# Servo_CAN_Node_REV-A.net
KiCad netlist of a schematic drawn in EAGLE
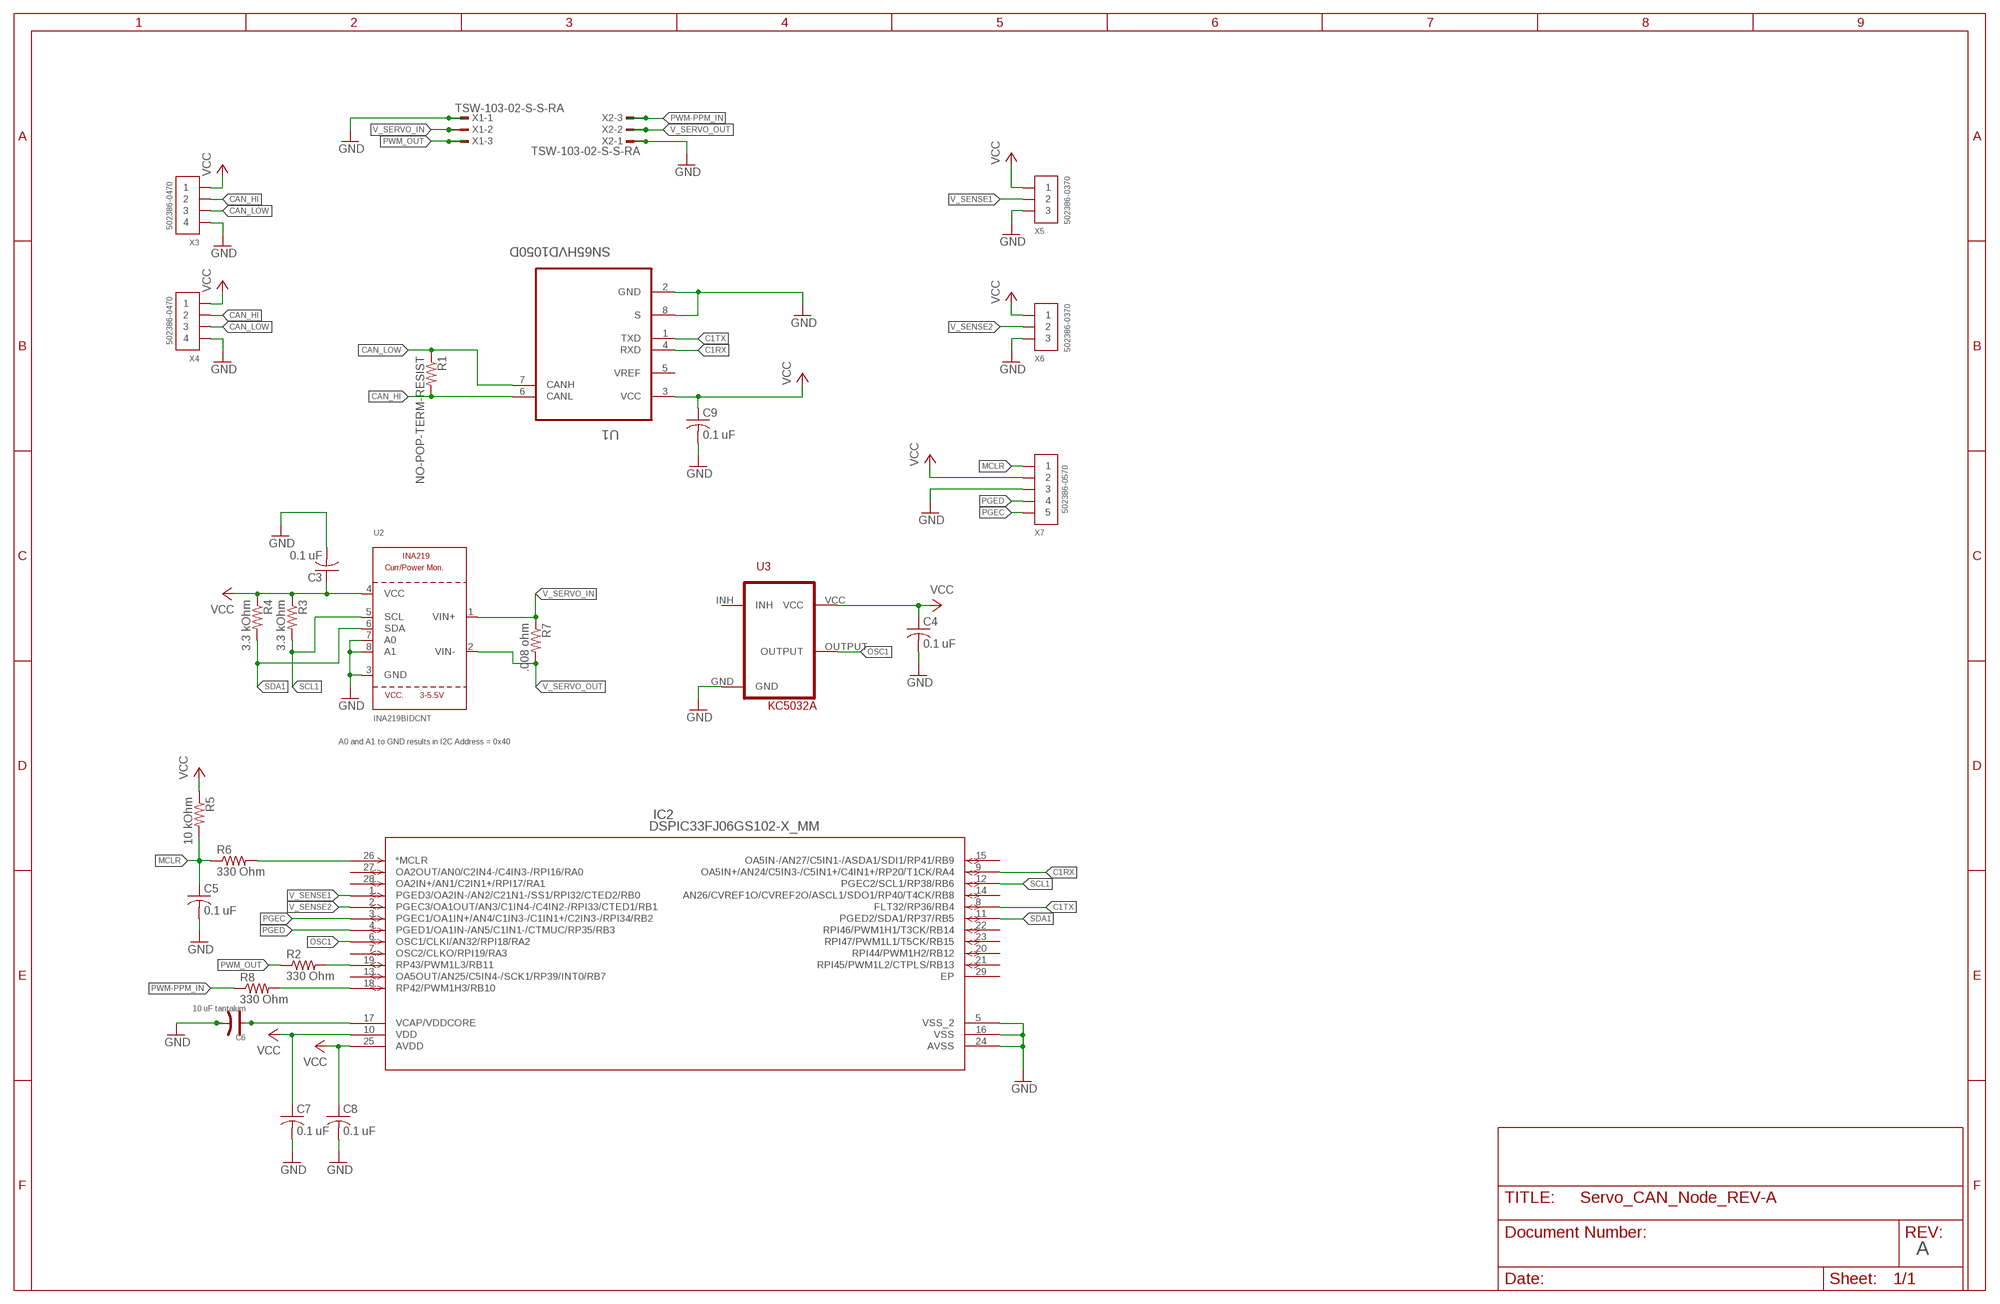
[diagram p0: schematic, sheet 1]

(export (version "E")
  (design (tool "Eeschema 10.0.6"))
  (components
    (comp (ref "C3")
      (value "0.1 uF")
      (footprint "eagle-import:C0402")
      (libsource (lib "eagle-import") (part "C-USC0402"))
    )
    (comp (ref "C4")
      (value "0.1 uF")
      (footprint "eagle-import:C0402")
      (libsource (lib "eagle-import") (part "C-USC0402"))
    )
    (comp (ref "C5")
      (value "0.1 uF")
      (footprint "eagle-import:C0402")
      (libsource (lib "eagle-import") (part "C-USC0402"))
    )
    (comp (ref "C6")
      (value "10 uF tantalum")
      (footprint "eagle-import:AVX-A")
      (libsource (lib "eagle-import") (part "CAP-POLAR-AVX-A"))
    )
    (comp (ref "C7")
      (value "0.1 uF")
      (footprint "eagle-import:C0402")
      (libsource (lib "eagle-import") (part "C-USC0402"))
    )
    (comp (ref "C8")
      (value "0.1 uF")
      (footprint "eagle-import:C0402")
      (libsource (lib "eagle-import") (part "C-USC0402"))
    )
    (comp (ref "C9")
      (value "0.1 uF")
      (footprint "eagle-import:C0402")
      (libsource (lib "eagle-import") (part "C-USC0402"))
    )
    (comp (ref "IC2")
      (value "DSPIC33FJ06GS102-X_MM")
      (footprint "eagle-import:QFN-S28_6X6MC")
      (libsource (lib "eagle-import") (part "DSPIC33FJ06GS102-X_MM"))
    )
    (comp (ref "R1")
      (value "NO-POP-TERM-RESIST")
      (footprint "eagle-import:R0402")
      (libsource (lib "eagle-import") (part "R-US_R0402"))
    )
    (comp (ref "R2")
      (value "330 Ohm")
      (footprint "eagle-import:R0402")
      (libsource (lib "eagle-import") (part "R-US_R0402"))
    )
    (comp (ref "R3")
      (value "3.3 kOhm")
      (footprint "eagle-import:R0402")
      (libsource (lib "eagle-import") (part "R-US_R0402"))
    )
    (comp (ref "R4")
      (value "3.3 kOhm")
      (footprint "eagle-import:R0402")
      (libsource (lib "eagle-import") (part "R-US_R0402"))
    )
    (comp (ref "R5")
      (value "10 kOhm")
      (footprint "eagle-import:R0402")
      (libsource (lib "eagle-import") (part "R-US_R0402"))
    )
    (comp (ref "R6")
      (value "330 Ohm")
      (footprint "eagle-import:R0402")
      (libsource (lib "eagle-import") (part "R-US_R0402"))
    )
    (comp (ref "R7")
      (value ".008 ohm")
      (footprint "eagle-import:R0805")
      (libsource (lib "eagle-import") (part "R-US_R0805"))
    )
    (comp (ref "R8")
      (value "330 Ohm")
      (footprint "eagle-import:R0402")
      (libsource (lib "eagle-import") (part "R-US_R0402"))
    )
    (comp (ref "U1")
      (value "SN65HVD1050D")
      (footprint "eagle-import:SOIC127P600X175-8N")
      (libsource (lib "eagle-import") (part "SN65HVD1050D"))
    )
    (comp (ref "U2")
      (value "INA219BIDCNT")
      (footprint "eagle-import:SOT23-8")
      (libsource (lib "eagle-import") (part "INA219"))
    )
    (comp (ref "U3")
      (value "KC5032A")
      (footprint "eagle-import:KC5032A")
      (libsource (lib "eagle-import") (part "KC5032A"))
    )
    (comp (ref "X1")
      (value "TSW-103-02-S-S-RA")
      (footprint "eagle-import:TSW-103-02-S-S-RA")
      (libsource (lib "eagle-import") (part "TSW-103-02-S-S-RA"))
    )
    (comp (ref "X2")
      (value "TSW-103-02-S-S-RA")
      (footprint "eagle-import:TSW-103-02-S-S-RA")
      (libsource (lib "eagle-import") (part "TSW-103-02-S-S-RA"))
    )
    (comp (ref "X3")
      (value "CONN_4-1-502386")
      (footprint "eagle-import:CM-502386-04")
      (libsource (lib "eagle-import") (part "CONN_4-1-502386"))
    )
    (comp (ref "X4")
      (value "CONN_4-1-502386")
      (footprint "eagle-import:CM-502386-04")
      (libsource (lib "eagle-import") (part "CONN_4-1-502386"))
    )
    (comp (ref "X5")
      (value "CONN_3-1-502386")
      (footprint "eagle-import:CM-502386-03")
      (libsource (lib "eagle-import") (part "CONN_3-1-502386"))
    )
    (comp (ref "X6")
      (value "CONN_3-1-502386")
      (footprint "eagle-import:CM-502386-03")
      (libsource (lib "eagle-import") (part "CONN_3-1-502386"))
    )
    (comp (ref "X7")
      (value "CONN_5-1-502386")
      (footprint "eagle-import:CM-502386-05")
      (libsource (lib "eagle-import") (part "CONN_5-1-502386"))
    )
  )
  (nets
    (net (code "1") (name "C1RX") (class "Default")
      (node (ref "IC2") (pin "9") (pinfunction "OA5IN+/AN24/C5IN3-/C5IN1+/C4IN1+/RP20/T1CK/RA4_9") (pintype "bidirectional"))
      (node (ref "U1") (pin "4") (pinfunction "RXD_4") (pintype "input"))
    )
    (net (code "2") (name "C1TX") (class "Default")
      (node (ref "IC2") (pin "8") (pinfunction "FLT32/RP36/RB4_8") (pintype "bidirectional"))
      (node (ref "U1") (pin "1") (pinfunction "TXD_1") (pintype "input"))
    )
    (net (code "3") (name "CAN_HI") (class "Default")
      (node (ref "R1") (pin "2") (pinfunction "2_2") (pintype "passive"))
      (node (ref "U1") (pin "6") (pinfunction "CANL_6") (pintype "output"))
      (node (ref "X3") (pin "2") (pinfunction "2_2") (pintype "bidirectional"))
      (node (ref "X4") (pin "2") (pinfunction "2_2") (pintype "bidirectional"))
    )
    (net (code "4") (name "CAN_LOW") (class "Default")
      (node (ref "R1") (pin "1") (pinfunction "1_1") (pintype "passive"))
      (node (ref "U1") (pin "7") (pinfunction "CANH_7") (pintype "output"))
      (node (ref "X3") (pin "3") (pinfunction "3_3") (pintype "bidirectional"))
      (node (ref "X4") (pin "3") (pinfunction "3_3") (pintype "bidirectional"))
    )
    (net (code "5") (name "GND") (class "Default")
      (node (ref "C3") (pin "2") (pinfunction "2_2") (pintype "passive"))
      (node (ref "C4") (pin "2") (pinfunction "2_2") (pintype "passive"))
      (node (ref "C5") (pin "2") (pinfunction "2_2") (pintype "passive"))
      (node (ref "C6") (pin "-") (pinfunction "-_-") (pintype "passive"))
      (node (ref "C7") (pin "2") (pinfunction "2_2") (pintype "passive"))
      (node (ref "C8") (pin "2") (pinfunction "2_2") (pintype "passive"))
      (node (ref "C9") (pin "2") (pinfunction "2_2") (pintype "passive"))
      (node (ref "IC2") (pin "16") (pinfunction "VSS_16") (pintype "power_in"))
      (node (ref "IC2") (pin "24") (pinfunction "AVSS_24") (pintype "power_in"))
      (node (ref "IC2") (pin "5") (pinfunction "VSS_2_5") (pintype "power_in"))
      (node (ref "U1") (pin "2") (pinfunction "GND_2") (pintype "passive"))
      (node (ref "U1") (pin "8") (pinfunction "S_8") (pintype "input"))
      (node (ref "U2") (pin "3") (pinfunction "GND_3") (pintype "bidirectional"))
      (node (ref "U2") (pin "7") (pinfunction "A0_7") (pintype "bidirectional"))
      (node (ref "U2") (pin "8") (pinfunction "A1_8") (pintype "bidirectional"))
      (node (ref "U3") (pin "GND") (pinfunction "GND_GND") (pintype "bidirectional"))
      (node (ref "X1") (pin "1") (pinfunction "1_1") (pintype "passive"))
      (node (ref "X2") (pin "1") (pinfunction "1_1") (pintype "passive"))
      (node (ref "X3") (pin "4") (pinfunction "4_4") (pintype "bidirectional"))
      (node (ref "X4") (pin "4") (pinfunction "4_4") (pintype "bidirectional"))
      (node (ref "X5") (pin "3") (pinfunction "3_3") (pintype "bidirectional"))
      (node (ref "X6") (pin "3") (pinfunction "3_3") (pintype "bidirectional"))
      (node (ref "X7") (pin "3") (pinfunction "3_3") (pintype "bidirectional"))
    )
    (net (code "6") (name "MCLR") (class "Default")
      (node (ref "C5") (pin "1") (pinfunction "1_1") (pintype "passive"))
      (node (ref "R5") (pin "2") (pinfunction "2_2") (pintype "passive"))
      (node (ref "R6") (pin "1") (pinfunction "1_1") (pintype "passive"))
      (node (ref "X7") (pin "1") (pinfunction "1_1") (pintype "bidirectional"))
    )
    (net (code "7") (name "Net-(IC2-*MCLR)") (class "Default")
      (node (ref "IC2") (pin "26") (pinfunction "*MCLR_26") (pintype "input"))
      (node (ref "R6") (pin "2") (pinfunction "2_2") (pintype "passive"))
    )
    (net (code "8") (name "Net-(IC2-RP42{slash}PWM1H3{slash}RB10)") (class "Default")
      (node (ref "IC2") (pin "18") (pinfunction "RP42/PWM1H3/RB10_18") (pintype "bidirectional"))
      (node (ref "R8") (pin "2") (pinfunction "2_2") (pintype "passive"))
    )
    (net (code "9") (name "Net-(IC2-RP43{slash}PWM1L3{slash}RB11)") (class "Default")
      (node (ref "IC2") (pin "19") (pinfunction "RP43/PWM1L3/RB11_19") (pintype "bidirectional"))
      (node (ref "R2") (pin "2") (pinfunction "2_2") (pintype "passive"))
    )
    (net (code "10") (name "Net-(IC2-VCAP{slash}VDDCORE)") (class "Default")
      (node (ref "C6") (pin "+") (pinfunction "+_+") (pintype "passive"))
      (node (ref "IC2") (pin "17") (pinfunction "VCAP/VDDCORE_17") (pintype "power_in"))
    )
    (net (code "11") (name "OSC1") (class "Default")
      (node (ref "IC2") (pin "6") (pinfunction "OSC1/CLKI/AN32/RPI18/RA2_6") (pintype "bidirectional"))
      (node (ref "U3") (pin "OUTPUT") (pinfunction "OUTPUT_OUTPUT") (pintype "bidirectional"))
    )
    (net (code "12") (name "PGEC") (class "Default")
      (node (ref "IC2") (pin "3") (pinfunction "PGEC1/OA1IN+/AN4/C1IN3-/C1IN1+/C2IN3-/RPI34/RB2_3") (pintype "bidirectional"))
      (node (ref "X7") (pin "5") (pinfunction "5_5") (pintype "bidirectional"))
    )
    (net (code "13") (name "PGED") (class "Default")
      (node (ref "IC2") (pin "4") (pinfunction "PGED1/OA1IN-/AN5/C1IN1-/CTMUC/RP35/RB3_4") (pintype "bidirectional"))
      (node (ref "X7") (pin "4") (pinfunction "4_4") (pintype "bidirectional"))
    )
    (net (code "14") (name "PWM-PPM_IN") (class "Default")
      (node (ref "R8") (pin "1") (pinfunction "1_1") (pintype "passive"))
      (node (ref "X2") (pin "3") (pinfunction "1_3") (pintype "passive"))
    )
    (net (code "15") (name "PWM_OUT") (class "Default")
      (node (ref "R2") (pin "1") (pinfunction "1_1") (pintype "passive"))
      (node (ref "X1") (pin "3") (pinfunction "1_3") (pintype "passive"))
    )
    (net (code "16") (name "SCL1") (class "Default")
      (node (ref "IC2") (pin "12") (pinfunction "PGEC2/SCL1/RP38/RB6_12") (pintype "bidirectional"))
      (node (ref "R3") (pin "2") (pinfunction "2_2") (pintype "passive"))
      (node (ref "U2") (pin "5") (pinfunction "SCL_5") (pintype "bidirectional"))
    )
    (net (code "17") (name "SDA1") (class "Default")
      (node (ref "IC2") (pin "11") (pinfunction "PGED2/SDA1/RP37/RB5_11") (pintype "bidirectional"))
      (node (ref "R4") (pin "2") (pinfunction "2_2") (pintype "passive"))
      (node (ref "U2") (pin "6") (pinfunction "SDA_6") (pintype "bidirectional"))
    )
    (net (code "18") (name "VCC") (class "Default")
      (node (ref "C3") (pin "1") (pinfunction "1_1") (pintype "passive"))
      (node (ref "C4") (pin "1") (pinfunction "1_1") (pintype "passive"))
      (node (ref "C7") (pin "1") (pinfunction "1_1") (pintype "passive"))
      (node (ref "C8") (pin "1") (pinfunction "1_1") (pintype "passive"))
      (node (ref "C9") (pin "1") (pinfunction "1_1") (pintype "passive"))
      (node (ref "IC2") (pin "10") (pinfunction "VDD_10") (pintype "power_in"))
      (node (ref "IC2") (pin "25") (pinfunction "AVDD_25") (pintype "power_in"))
      (node (ref "R3") (pin "1") (pinfunction "1_1") (pintype "passive"))
      (node (ref "R4") (pin "1") (pinfunction "1_1") (pintype "passive"))
      (node (ref "R5") (pin "1") (pinfunction "1_1") (pintype "passive"))
      (node (ref "U1") (pin "3") (pinfunction "VCC_3") (pintype "power_in"))
      (node (ref "U2") (pin "4") (pinfunction "VCC_4") (pintype "bidirectional"))
      (node (ref "U3") (pin "VCC") (pinfunction "VCC_VCC") (pintype "bidirectional"))
      (node (ref "X3") (pin "1") (pinfunction "1_1") (pintype "bidirectional"))
      (node (ref "X4") (pin "1") (pinfunction "1_1") (pintype "bidirectional"))
      (node (ref "X5") (pin "1") (pinfunction "1_1") (pintype "bidirectional"))
      (node (ref "X6") (pin "1") (pinfunction "1_1") (pintype "bidirectional"))
      (node (ref "X7") (pin "2") (pinfunction "2_2") (pintype "bidirectional"))
    )
    (net (code "19") (name "V_SENSE1") (class "Default")
      (node (ref "IC2") (pin "1") (pinfunction "PGED3/OA2IN-/AN2/C21N1-/SS1/RPI32/CTED2/RB0_1") (pintype "bidirectional"))
      (node (ref "X5") (pin "2") (pinfunction "2_2") (pintype "bidirectional"))
    )
    (net (code "20") (name "V_SENSE2") (class "Default")
      (node (ref "IC2") (pin "2") (pinfunction "PGEC3/OA1OUT/AN3/C1IN4-/C4IN2-/RPI33/CTED1/RB1_2") (pintype "bidirectional"))
      (node (ref "X6") (pin "2") (pinfunction "2_2") (pintype "bidirectional"))
    )
    (net (code "21") (name "V_SERVO_IN") (class "Default")
      (node (ref "R7") (pin "1") (pinfunction "1_1") (pintype "passive"))
      (node (ref "U2") (pin "1") (pinfunction "VIN+_1") (pintype "bidirectional"))
      (node (ref "X1") (pin "2") (pinfunction "1_2") (pintype "passive"))
    )
    (net (code "22") (name "V_SERVO_OUT") (class "Default")
      (node (ref "R7") (pin "2") (pinfunction "2_2") (pintype "passive"))
      (node (ref "U2") (pin "2") (pinfunction "VIN-_2") (pintype "bidirectional"))
      (node (ref "X2") (pin "2") (pinfunction "1_2") (pintype "passive"))
    )
    (net (code "23") (name "unconnected-(IC2-AN26{slash}CVREF1O{slash}CVREF2O{slash}ASCL1{slash}SDO1{slash}RP40{slash}T4CK{slash}RB8-Pad14)") (class "Default")
      (node (ref "IC2") (pin "14") (pinfunction "AN26/CVREF1O/CVREF2O/ASCL1/SDO1/RP40/T4CK/RB8_14") (pintype "bidirectional"))
    )
    (net (code "24") (name "unconnected-(IC2-EP-Pad29)") (class "Default")
      (node (ref "IC2") (pin "29") (pinfunction "EP_29") (pintype "passive"))
    )
    (net (code "25") (name "unconnected-(IC2-OA2IN+{slash}AN1{slash}C2IN1+{slash}RPI17{slash}RA1-Pad28)") (class "Default")
      (node (ref "IC2") (pin "28") (pinfunction "OA2IN+/AN1/C2IN1+/RPI17/RA1_28") (pintype "bidirectional"))
    )
    (net (code "26") (name "unconnected-(IC2-OA2OUT{slash}AN0{slash}C2IN4-{slash}C4IN3-{slash}RPI16{slash}RA0-Pad27)") (class "Default")
      (node (ref "IC2") (pin "27") (pinfunction "OA2OUT/AN0/C2IN4-/C4IN3-/RPI16/RA0_27") (pintype "bidirectional"))
    )
    (net (code "27") (name "unconnected-(IC2-OA5IN-{slash}AN27{slash}C5IN1-{slash}ASDA1{slash}SDI1{slash}RP41{slash}RB9-Pad15)") (class "Default")
      (node (ref "IC2") (pin "15") (pinfunction "OA5IN-/AN27/C5IN1-/ASDA1/SDI1/RP41/RB9_15") (pintype "bidirectional"))
    )
    (net (code "28") (name "unconnected-(IC2-OA5OUT{slash}AN25{slash}C5IN4-{slash}SCK1{slash}RP39{slash}INT0{slash}RB7-Pad13)") (class "Default")
      (node (ref "IC2") (pin "13") (pinfunction "OA5OUT/AN25/C5IN4-/SCK1/RP39/INT0/RB7_13") (pintype "bidirectional"))
    )
    (net (code "29") (name "unconnected-(IC2-OSC2{slash}CLKO{slash}RPI19{slash}RA3-Pad7)") (class "Default")
      (node (ref "IC2") (pin "7") (pinfunction "OSC2/CLKO/RPI19/RA3_7") (pintype "bidirectional"))
    )
    (net (code "30") (name "unconnected-(IC2-RPI44{slash}PWM1H2{slash}RB12-Pad20)") (class "Default")
      (node (ref "IC2") (pin "20") (pinfunction "RPI44/PWM1H2/RB12_20") (pintype "bidirectional"))
    )
    (net (code "31") (name "unconnected-(IC2-RPI45{slash}PWM1L2{slash}CTPLS{slash}RB13-Pad21)") (class "Default")
      (node (ref "IC2") (pin "21") (pinfunction "RPI45/PWM1L2/CTPLS/RB13_21") (pintype "bidirectional"))
    )
    (net (code "32") (name "unconnected-(IC2-RPI46{slash}PWM1H1{slash}T3CK{slash}RB14-Pad22)") (class "Default")
      (node (ref "IC2") (pin "22") (pinfunction "RPI46/PWM1H1/T3CK/RB14_22") (pintype "bidirectional"))
    )
    (net (code "33") (name "unconnected-(IC2-RPI47{slash}PWM1L1{slash}T5CK{slash}RB15-Pad23)") (class "Default")
      (node (ref "IC2") (pin "23") (pinfunction "RPI47/PWM1L1/T5CK/RB15_23") (pintype "bidirectional"))
    )
    (net (code "34") (name "unconnected-(U1-VREF-Pad5)") (class "Default")
      (node (ref "U1") (pin "5") (pinfunction "VREF_5") (pintype "input"))
    )
    (net (code "35") (name "unconnected-(U3-PadINH)") (class "Default")
      (node (ref "U3") (pin "INH") (pinfunction "INH_INH") (pintype "bidirectional"))
    )
  )
)
